# STM32F4layout.net
KiCad netlist of a schematic drawn in EAGLE
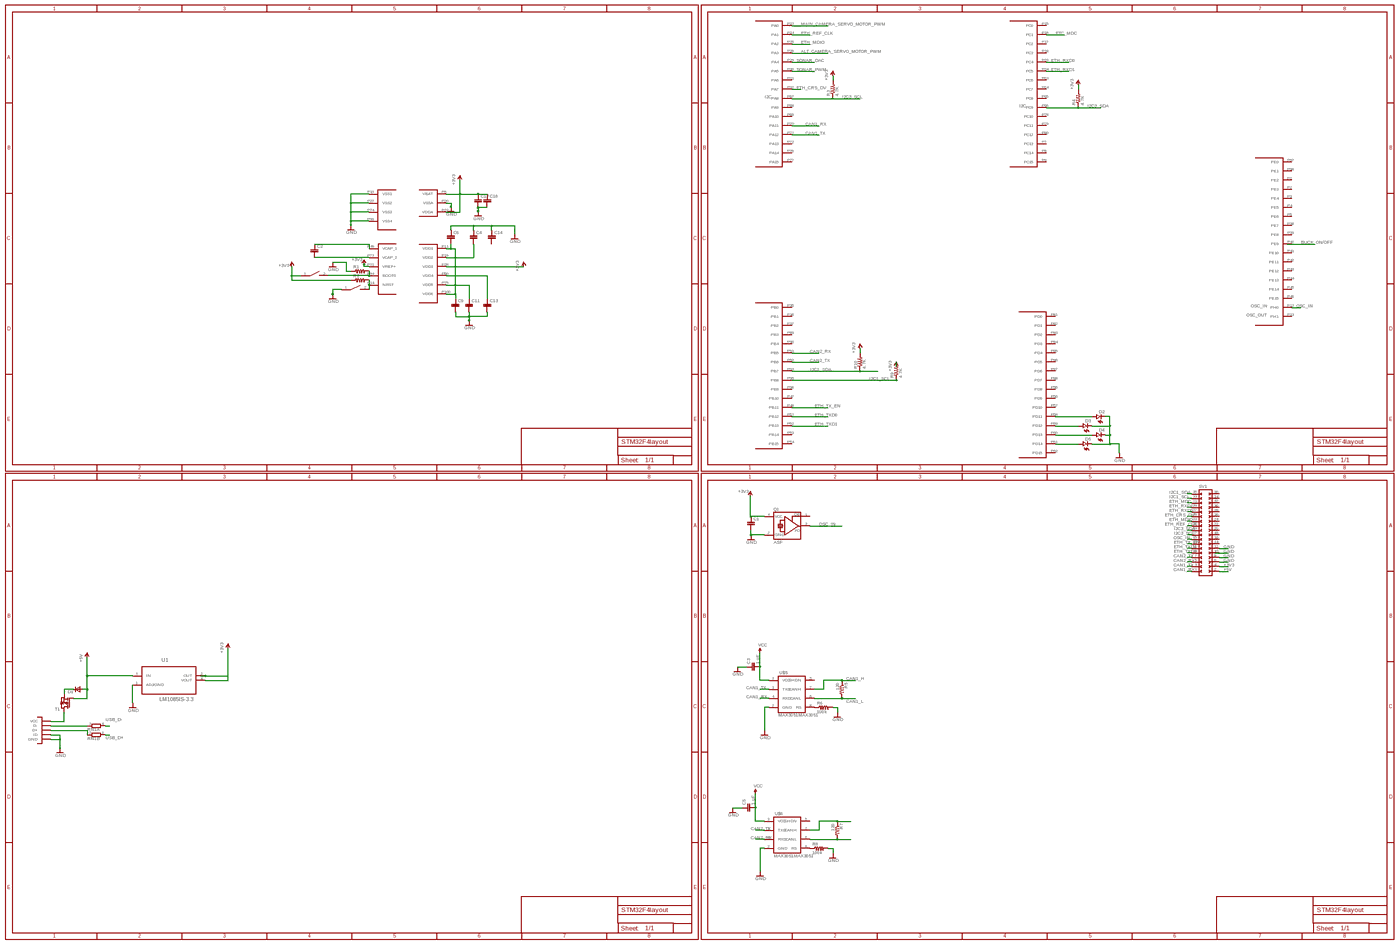
[diagram p0: schematic, sheet 1, overview]
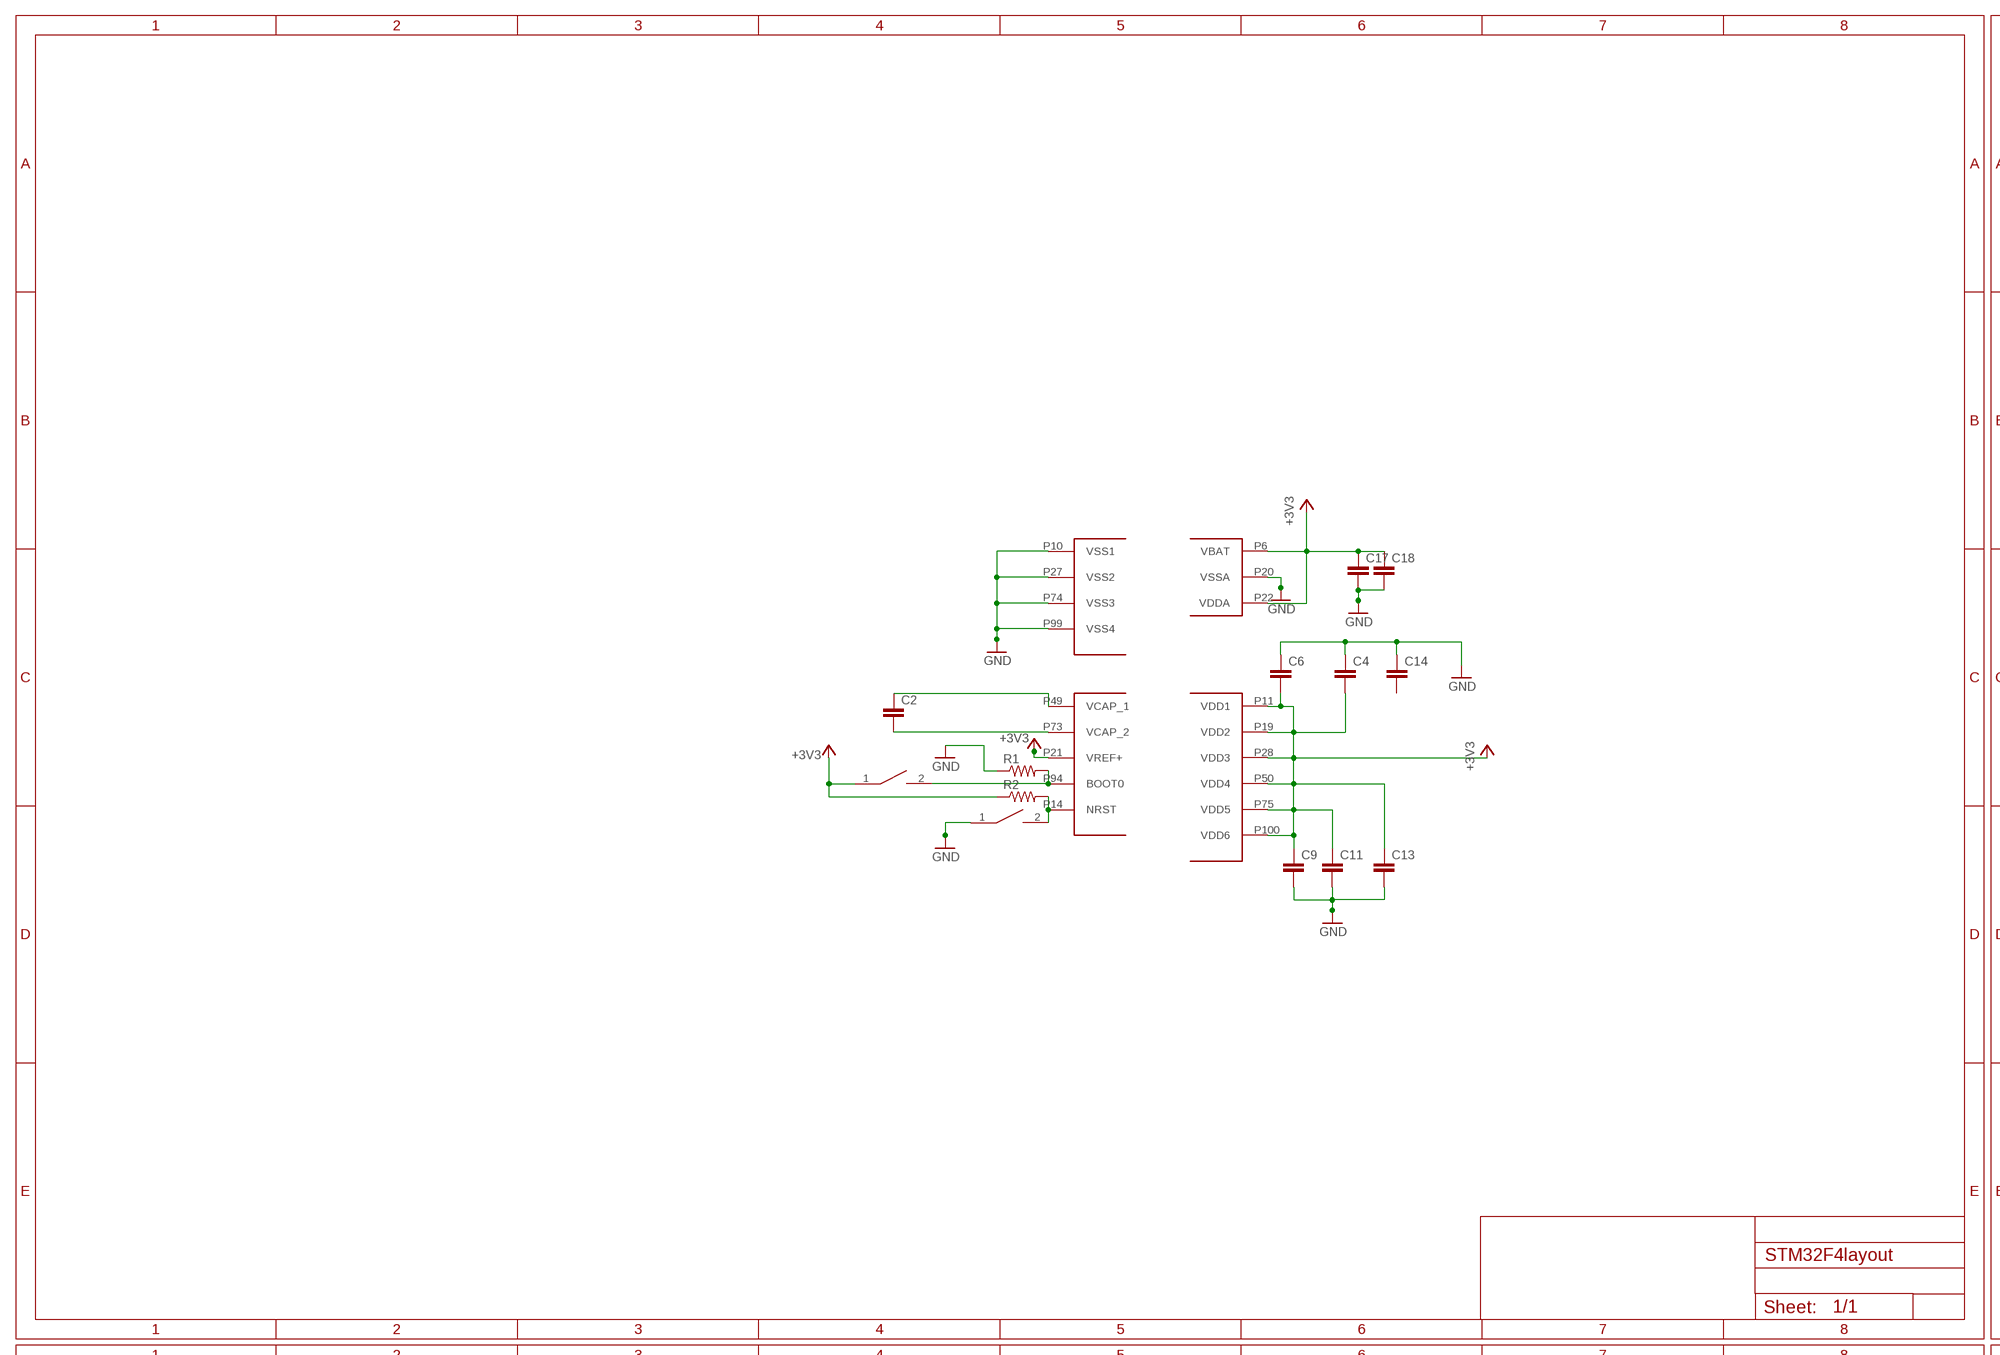
[diagram p1: schematic, sheet 1, part 1 of 4]
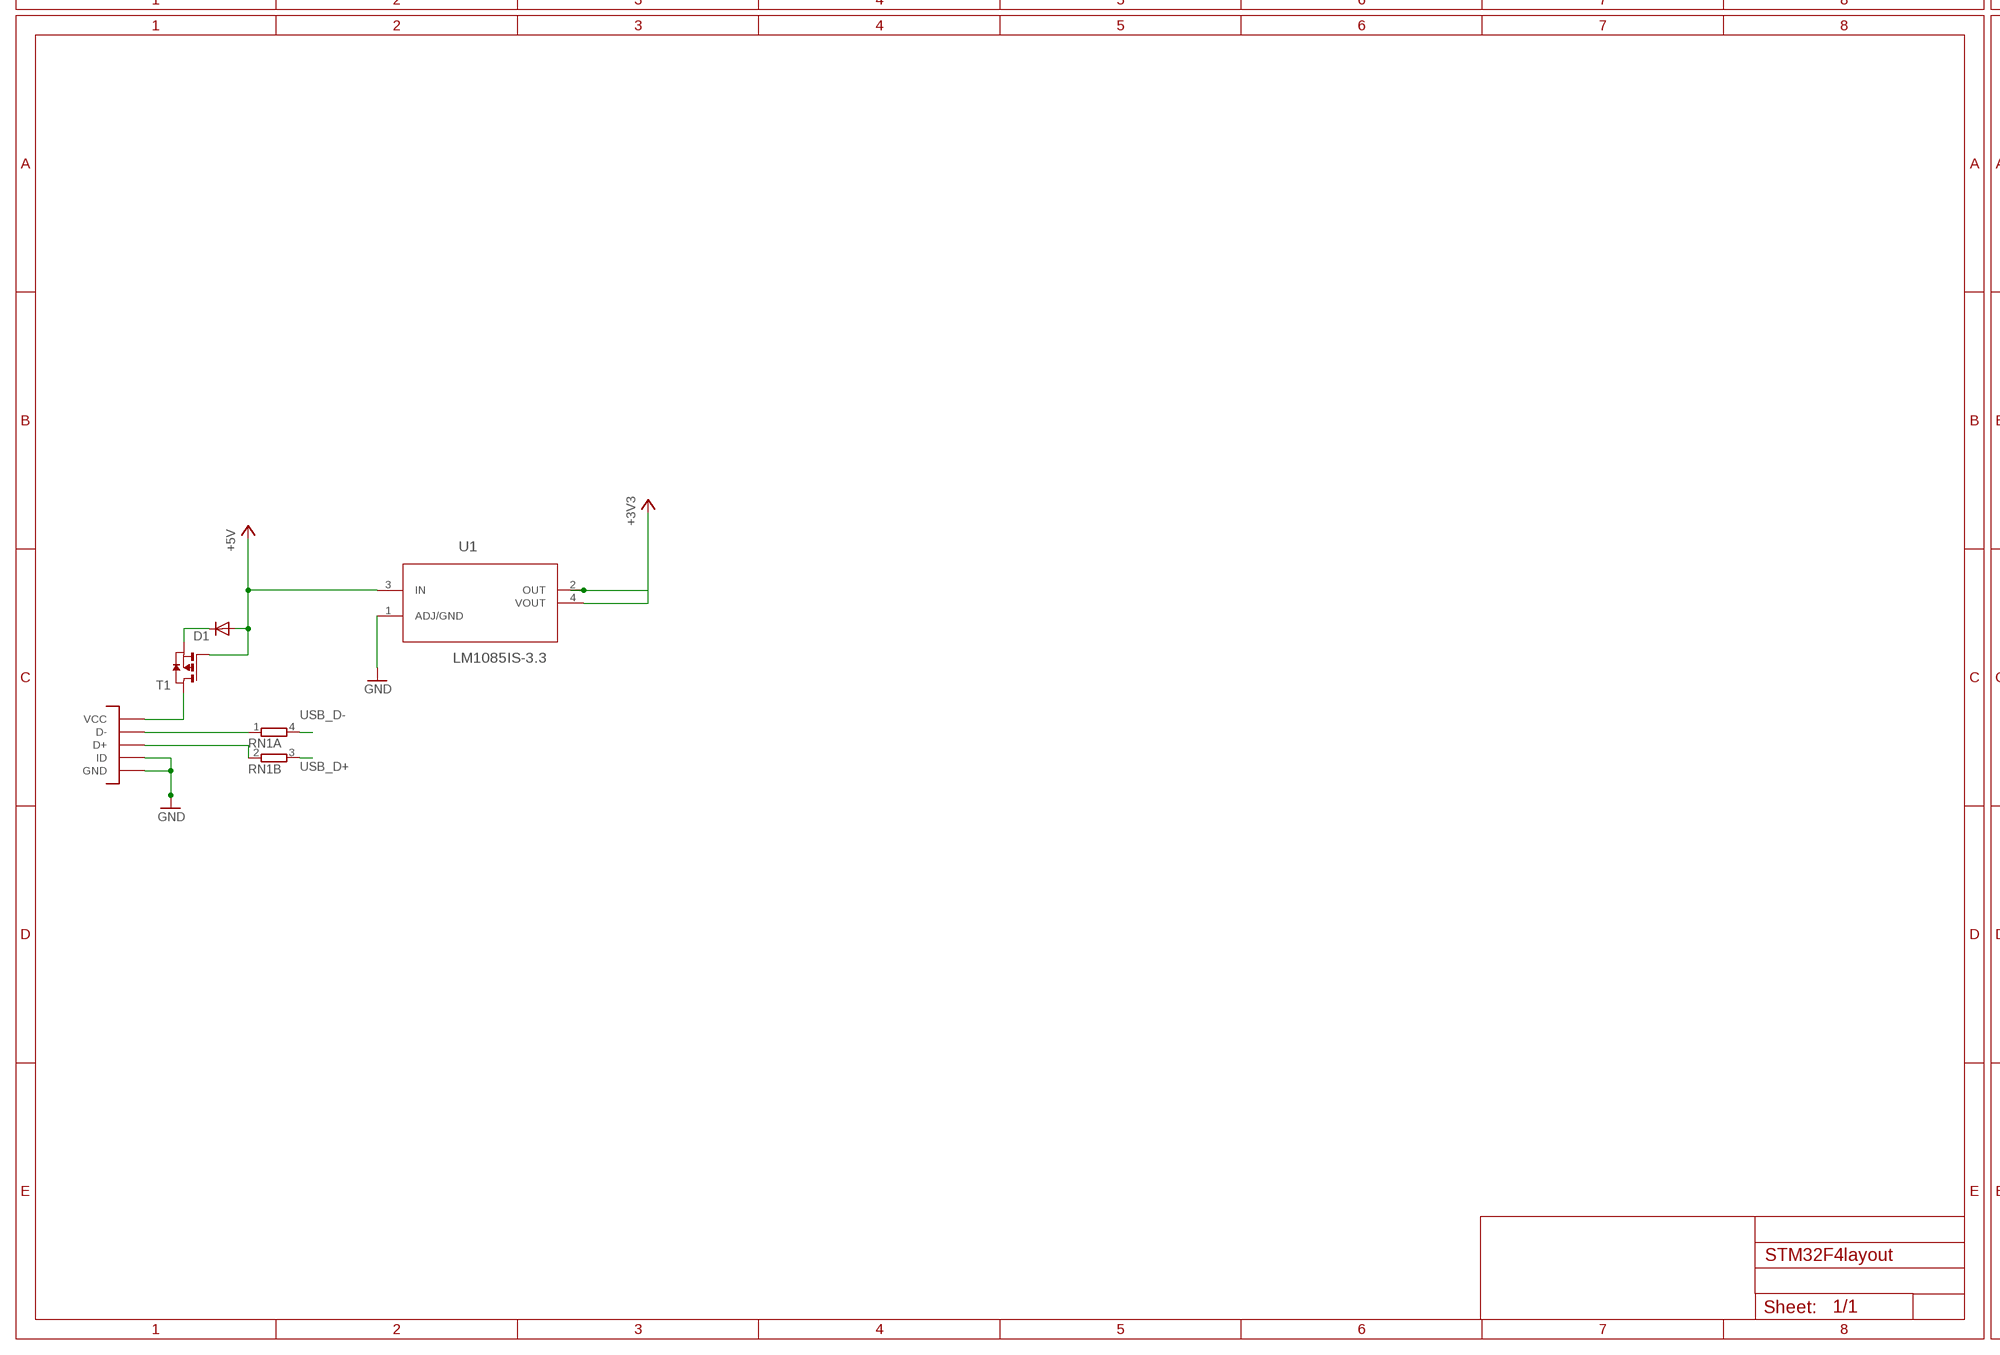
[diagram p2: schematic, sheet 1, part 2 of 4]
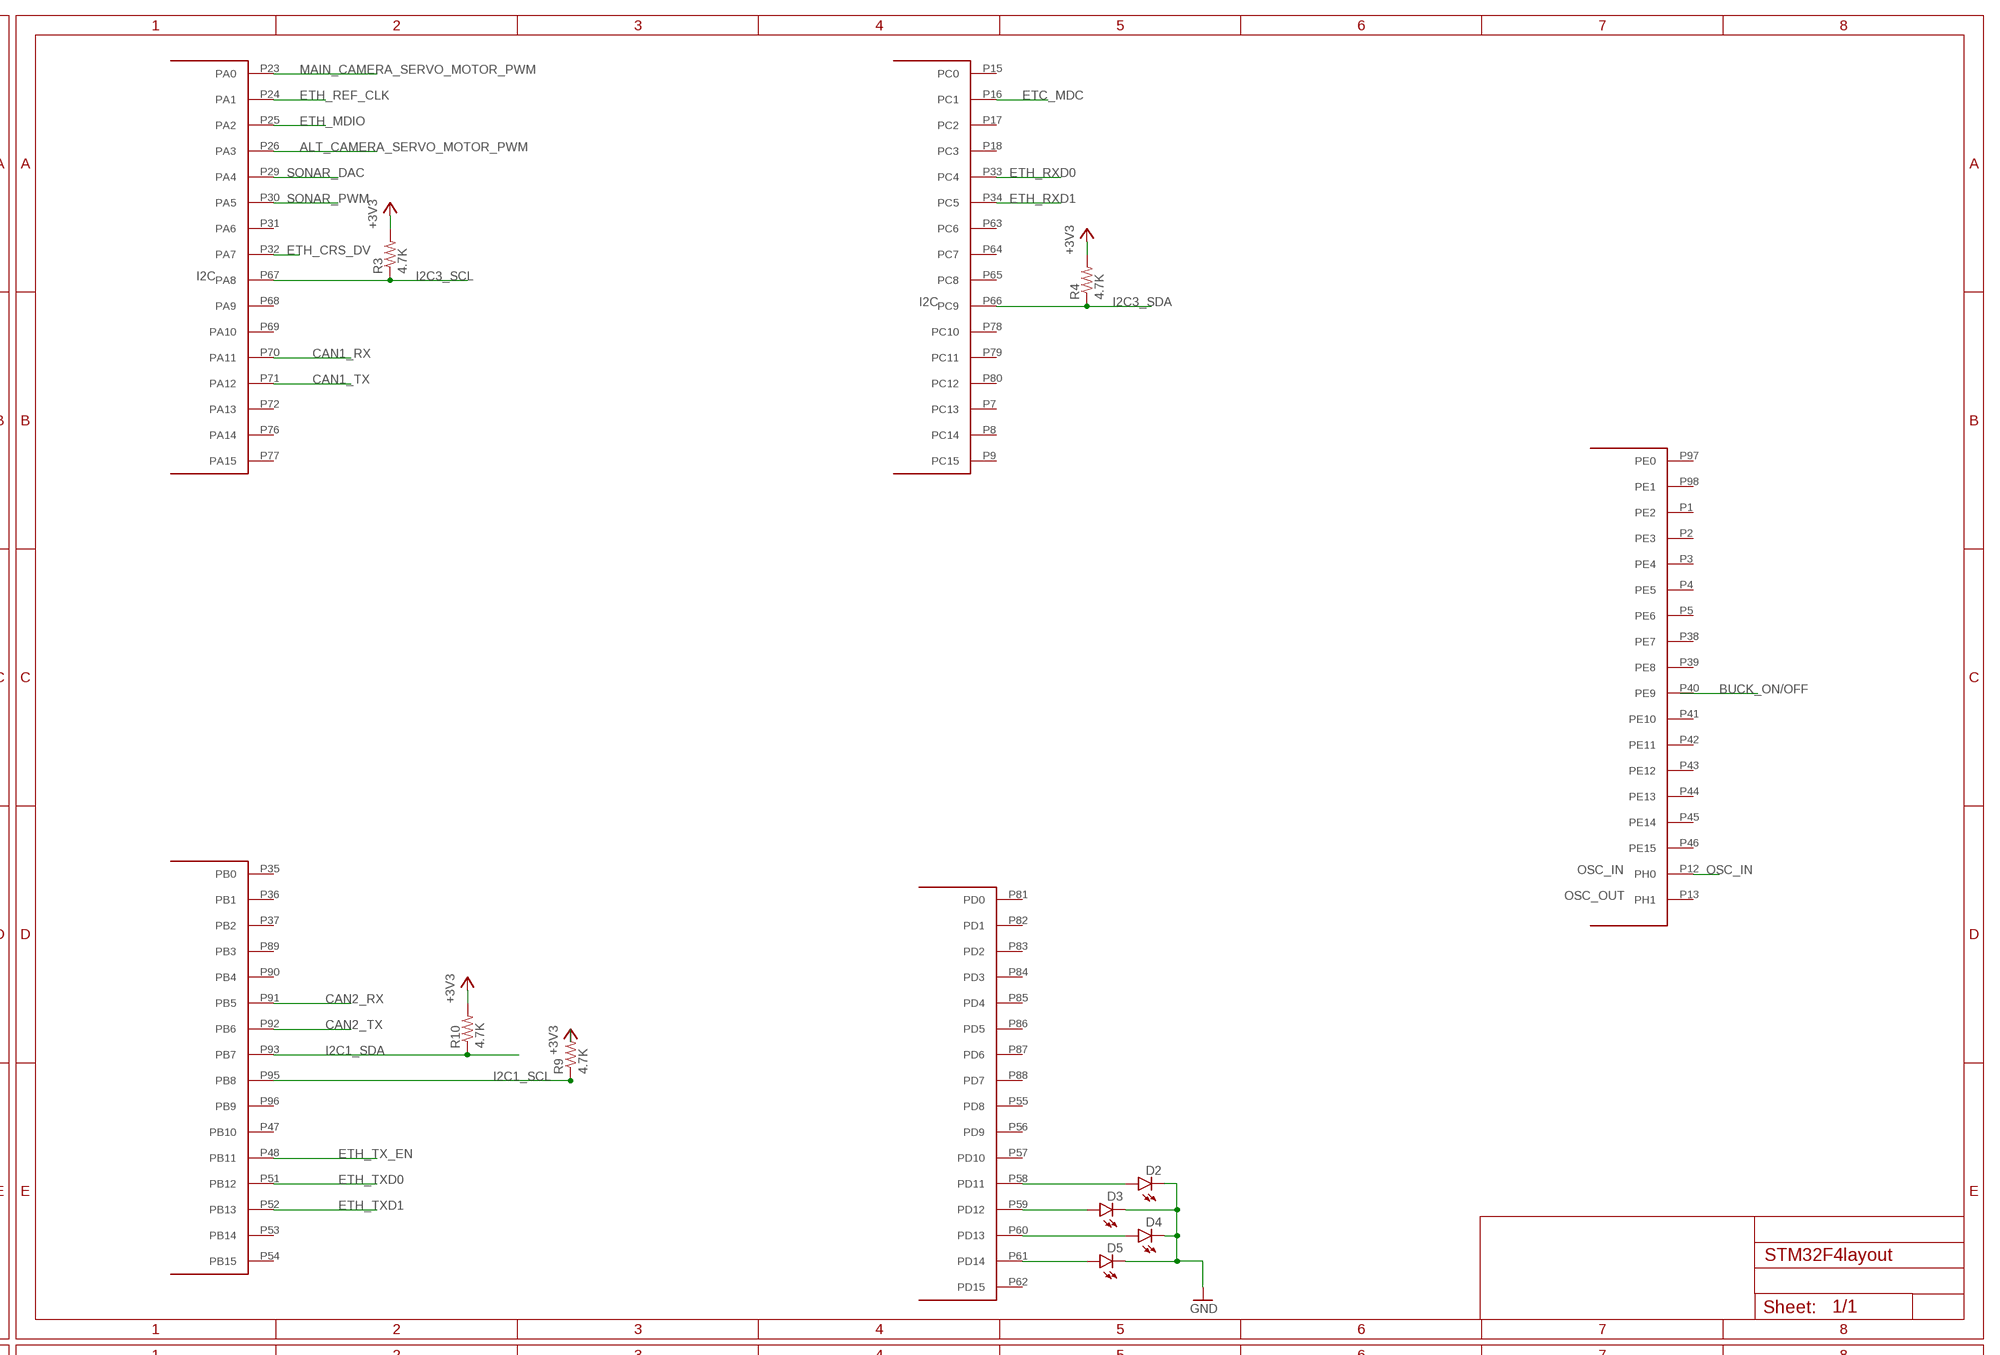
[diagram p3: schematic, sheet 1, part 3 of 4]
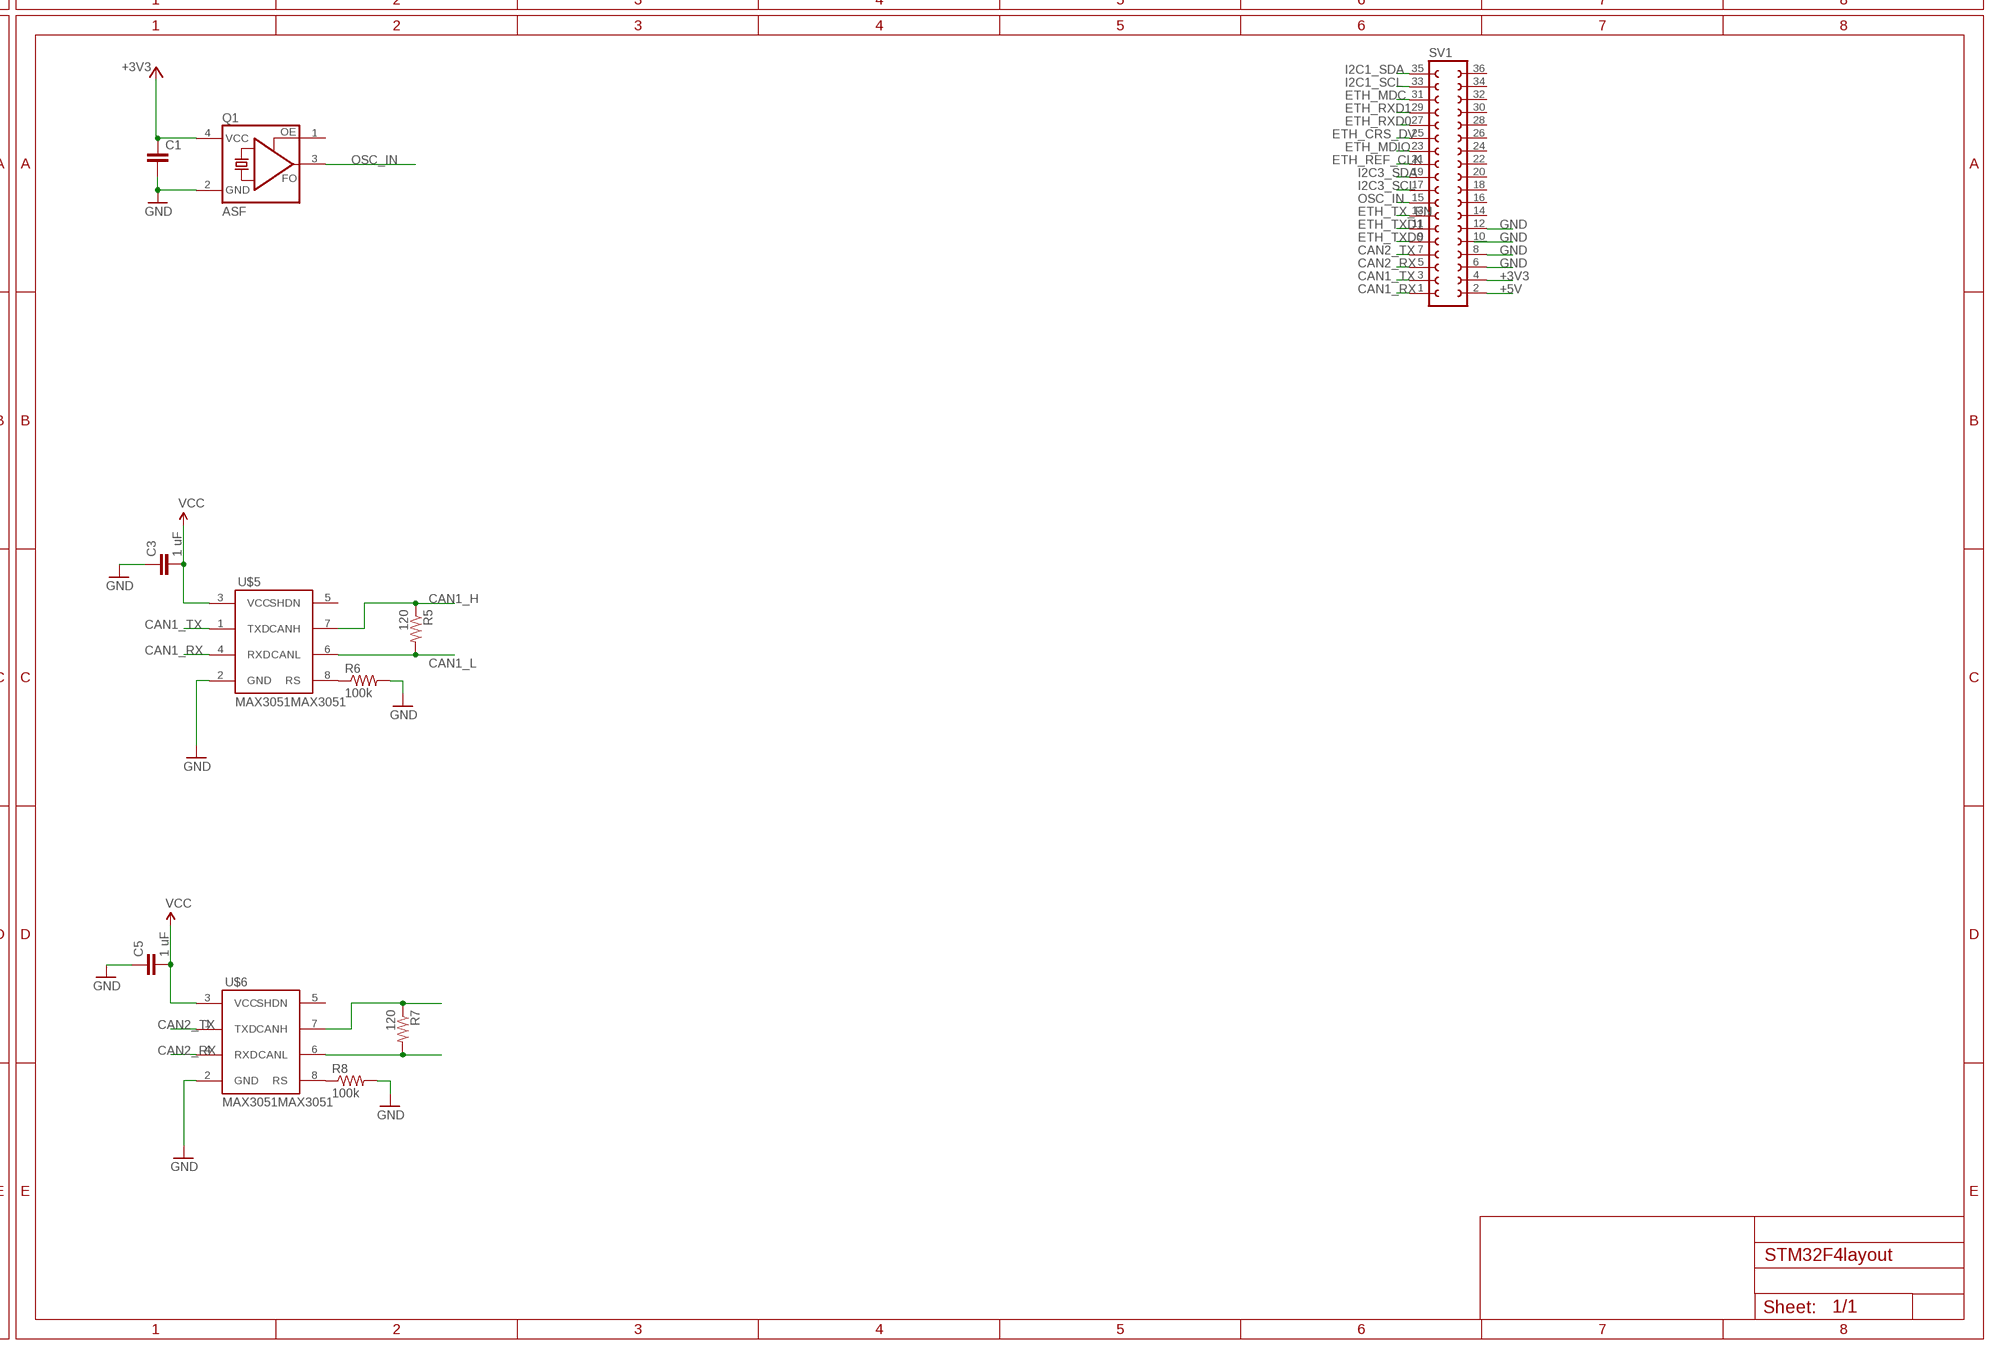
[diagram p4: schematic, sheet 1, part 4 of 4]

(export (version "E")
  (design (tool "Eeschema 10.0.6"))
  (components
    (comp (ref "C1")
      (value "CAP0603-CAP")
      (footprint "eagle-import:0603-CAP")
      (libsource (lib "eagle-import") (part "CAP0603-CAP"))
    )
    (comp (ref "C2")
      (value "CAP0603-CAP")
      (footprint "eagle-import:0603-CAP")
      (libsource (lib "eagle-import") (part "CAP0603-CAP"))
    )
    (comp (ref "C3")
      (value "1 uF")
      (footprint "eagle-import:C2.5-3")
      (libsource (lib "eagle-import") (part "C2,5-3"))
    )
    (comp (ref "C4")
      (value "CAP0603-CAP")
      (footprint "eagle-import:0603-CAP")
      (libsource (lib "eagle-import") (part "CAP0603-CAP"))
    )
    (comp (ref "C5")
      (value "1 uF")
      (footprint "eagle-import:C2.5-3")
      (libsource (lib "eagle-import") (part "C2,5-3"))
    )
    (comp (ref "C6")
      (value "CAP0603-CAP")
      (footprint "eagle-import:0603-CAP")
      (libsource (lib "eagle-import") (part "CAP0603-CAP"))
    )
    (comp (ref "C9")
      (value "CAP0603-CAP")
      (footprint "eagle-import:0603-CAP")
      (libsource (lib "eagle-import") (part "CAP0603-CAP"))
    )
    (comp (ref "C11")
      (value "CAP0603-CAP")
      (footprint "eagle-import:0603-CAP")
      (libsource (lib "eagle-import") (part "CAP0603-CAP"))
    )
    (comp (ref "C13")
      (value "CAP0603-CAP")
      (footprint "eagle-import:0603-CAP")
      (libsource (lib "eagle-import") (part "CAP0603-CAP"))
    )
    (comp (ref "C14")
      (value "CAP0603-CAP")
      (footprint "eagle-import:0603-CAP")
      (libsource (lib "eagle-import") (part "CAP0603-CAP"))
    )
    (comp (ref "C17")
      (value "CAP0603-CAP")
      (footprint "eagle-import:0603-CAP")
      (libsource (lib "eagle-import") (part "CAP0603-CAP"))
    )
    (comp (ref "C18")
      (value "CAP0603-CAP")
      (footprint "eagle-import:0603-CAP")
      (libsource (lib "eagle-import") (part "CAP0603-CAP"))
    )
    (comp (ref "D1")
      (value "DIODE-DO-214AC")
      (footprint "eagle-import:DO-214AC")
      (libsource (lib "eagle-import") (part "DIODE-DO-214AC"))
    )
    (comp (ref "D2")
      (value "LED0603")
      (footprint "eagle-import:LED-0603")
      (libsource (lib "eagle-import") (part "LED0603"))
    )
    (comp (ref "D3")
      (value "LED0603")
      (footprint "eagle-import:LED-0603")
      (libsource (lib "eagle-import") (part "LED0603"))
    )
    (comp (ref "D4")
      (value "LED0603")
      (footprint "eagle-import:LED-0603")
      (libsource (lib "eagle-import") (part "LED0603"))
    )
    (comp (ref "D5")
      (value "LED0603")
      (footprint "eagle-import:LED-0603")
      (libsource (lib "eagle-import") (part "LED0603"))
    )
    (comp (ref "Q1")
      (value "ASF")
      (footprint "eagle-import:ASF")
      (libsource (lib "eagle-import") (part "ASF"))
    )
    (comp (ref "R1")
      (value "RESISTOR0603-RES")
      (footprint "eagle-import:0603-RES")
      (libsource (lib "eagle-import") (part "RESISTOR0603-RES"))
    )
    (comp (ref "R2")
      (value "RESISTOR0603-RES")
      (footprint "eagle-import:0603-RES")
      (libsource (lib "eagle-import") (part "RESISTOR0603-RES"))
    )
    (comp (ref "R3")
      (value "4.7K")
      (footprint "eagle-import:0603-RES")
      (libsource (lib "eagle-import") (part "RESISTOR0603-RES"))
    )
    (comp (ref "R4")
      (value "4.7K")
      (footprint "eagle-import:0603-RES")
      (libsource (lib "eagle-import") (part "RESISTOR0603-RES"))
    )
    (comp (ref "R5")
      (value "120")
      (footprint "eagle-import:0204V")
      (libsource (lib "eagle-import") (part "R-US_0204/2V"))
    )
    (comp (ref "R6")
      (value "100k")
      (footprint "eagle-import:0204V")
      (libsource (lib "eagle-import") (part "R-US_0204/2V"))
    )
    (comp (ref "R7")
      (value "120")
      (footprint "eagle-import:0204V")
      (libsource (lib "eagle-import") (part "R-US_0204/2V"))
    )
    (comp (ref "R8")
      (value "100k")
      (footprint "eagle-import:0204V")
      (libsource (lib "eagle-import") (part "R-US_0204/2V"))
    )
    (comp (ref "R9")
      (value "4.7K")
      (footprint "eagle-import:0603-RES")
      (libsource (lib "eagle-import") (part "RESISTOR0603-RES"))
    )
    (comp (ref "R10")
      (value "4.7K")
      (footprint "eagle-import:0603-RES")
      (libsource (lib "eagle-import") (part "RESISTOR0603-RES"))
    )
    (comp (ref "RN1")
      (value "2R-NEXBV4V")
      (footprint "eagle-import:EXBV4V")
      (fields (field (name "MF") "Rohm Semiconductor") (field (name "MPN") "MNR12ERAPJ220"))
      (libsource (lib "eagle-import") (part "2R-NEXBV4V"))
    )
    (comp (ref "SV1")
      (value "FE18-2")
      (footprint "eagle-import:FE18-2")
      (libsource (lib "eagle-import") (part "FE18-2"))
    )
    (comp (ref "T1")
      (value "FDN340P")
      (footprint "eagle-import:SOT-23")
      (libsource (lib "eagle-import") (part "FDN340P"))
    )
    (comp (ref "U$1")
      (value "STM32F4")
      (footprint "eagle-import:LQFP100")
      (libsource (lib "eagle-import") (part "STM32F4"))
    )
    (comp (ref "U$2")
      (value "SWITCH")
      (footprint "eagle-import:SW_2512")
      (libsource (lib "eagle-import") (part "SWITCH"))
    )
    (comp (ref "U$3")
      (value "SWITCH")
      (footprint "eagle-import:SW_2512")
      (libsource (lib "eagle-import") (part "SWITCH"))
    )
    (comp (ref "U$4")
      (value "MICROUSB")
      (footprint "eagle-import:MICRO_B")
      (libsource (lib "eagle-import") (part "MICROUSB"))
    )
    (comp (ref "U$5")
      (value "MAX3051MAX3051")
      (footprint "eagle-import:SOT23-8L")
      (libsource (lib "eagle-import") (part "MAX3051MAX3051"))
    )
    (comp (ref "U$6")
      (value "MAX3051MAX3051")
      (footprint "eagle-import:SOT23-8L")
      (libsource (lib "eagle-import") (part "MAX3051MAX3051"))
    )
    (comp (ref "U1")
      (value "LM1085IS-3.3")
      (footprint "eagle-import:TO254P1435X457-3N")
      (libsource (lib "eagle-import") (part "LM1085IS-3.3"))
    )
  )
  (nets
    (net (code "1") (name "+3V3") (class "Default")
      (node (ref "C11") (pin "1") (pinfunction "1_1") (pintype "passive"))
      (node (ref "C13") (pin "1") (pinfunction "1_1") (pintype "passive"))
      (node (ref "C17") (pin "1") (pinfunction "1_1") (pintype "passive"))
      (node (ref "C18") (pin "1") (pinfunction "1_1") (pintype "passive"))
      (node (ref "C4") (pin "2") (pinfunction "2_2") (pintype "passive"))
      (node (ref "C6") (pin "2") (pinfunction "2_2") (pintype "passive"))
      (node (ref "C9") (pin "1") (pinfunction "1_1") (pintype "passive"))
      (node (ref "R10") (pin "2") (pinfunction "2_2") (pintype "passive"))
      (node (ref "R2") (pin "1") (pinfunction "1_1") (pintype "passive"))
      (node (ref "R3") (pin "2") (pinfunction "2_2") (pintype "passive"))
      (node (ref "R4") (pin "2") (pinfunction "2_2") (pintype "passive"))
      (node (ref "R9") (pin "2") (pinfunction "2_2") (pintype "passive"))
      (node (ref "SV1") (pin "4") (pinfunction "4_4") (pintype "passive"))
      (node (ref "U$1") (pin "P100") (pinfunction "VDD6_P100") (pintype "bidirectional"))
      (node (ref "U$1") (pin "P11") (pinfunction "VDD1_P11") (pintype "bidirectional"))
      (node (ref "U$1") (pin "P19") (pinfunction "VDD2_P19") (pintype "bidirectional"))
      (node (ref "U$1") (pin "P21") (pinfunction "VREF+_P21") (pintype "bidirectional"))
      (node (ref "U$1") (pin "P22") (pinfunction "VDDA_P22") (pintype "bidirectional"))
      (node (ref "U$1") (pin "P28") (pinfunction "VDD3_P28") (pintype "bidirectional"))
      (node (ref "U$1") (pin "P50") (pinfunction "VDD4_P50") (pintype "bidirectional"))
      (node (ref "U$1") (pin "P6") (pinfunction "VBAT_P6") (pintype "bidirectional"))
      (node (ref "U$1") (pin "P75") (pinfunction "VDD5_P75") (pintype "bidirectional"))
      (node (ref "U$3") (pin "1") (pinfunction "P$1_1") (pintype "bidirectional"))
      (node (ref "U1") (pin "2") (pinfunction "OUT_2") (pintype "output"))
      (node (ref "U1") (pin "4") (pinfunction "VOUT_4") (pintype "output"))
    )
    (net (code "2") (name "+5V") (class "Default")
      (node (ref "D1") (pin "A") (pinfunction "A_A") (pintype "passive"))
      (node (ref "SV1") (pin "2") (pinfunction "2_2") (pintype "passive"))
      (node (ref "T1") (pin "3") (pinfunction "G_3") (pintype "passive"))
      (node (ref "U1") (pin "3") (pinfunction "IN_3") (pintype "power_in"))
    )
    (net (code "3") (name "/ALT_CAMERA_SERVO_MOTOR_PWM") (class "Default")
      (node (ref "U$1") (pin "P26") (pinfunction "PA3_P26") (pintype "bidirectional"))
    )
    (net (code "5") (name "/CAN1_H") (class "Default")
      (node (ref "R5") (pin "1") (pinfunction "1_1") (pintype "passive"))
      (node (ref "U$5") (pin "7") (pinfunction "CANH_7") (pintype "bidirectional"))
    )
    (net (code "6") (name "/CAN1_L") (class "Default")
      (node (ref "R5") (pin "2") (pinfunction "2_2") (pintype "passive"))
      (node (ref "U$5") (pin "6") (pinfunction "CANL_6") (pintype "bidirectional"))
    )
    (net (code "7") (name "/CAN1_RX") (class "Default")
      (node (ref "RN1") (pin "4") (pinfunction "2_4") (pintype "passive"))
      (node (ref "SV1") (pin "1") (pinfunction "1_1") (pintype "passive"))
      (node (ref "U$1") (pin "P70") (pinfunction "PA11_P70") (pintype "bidirectional"))
      (node (ref "U$5") (pin "4") (pinfunction "RXD_4") (pintype "bidirectional"))
    )
    (net (code "8") (name "/CAN1_TX") (class "Default")
      (node (ref "RN1") (pin "3") (pinfunction "2_3") (pintype "passive"))
      (node (ref "SV1") (pin "3") (pinfunction "3_3") (pintype "passive"))
      (node (ref "U$1") (pin "P71") (pinfunction "PA12_P71") (pintype "bidirectional"))
      (node (ref "U$5") (pin "1") (pinfunction "TXD_1") (pintype "bidirectional"))
    )
    (net (code "9") (name "/CAN2_RX") (class "Default")
      (node (ref "SV1") (pin "5") (pinfunction "5_5") (pintype "passive"))
      (node (ref "U$1") (pin "P91") (pinfunction "PB5_P91") (pintype "bidirectional"))
      (node (ref "U$6") (pin "4") (pinfunction "RXD_4") (pintype "bidirectional"))
    )
    (net (code "10") (name "/CAN2_TX") (class "Default")
      (node (ref "SV1") (pin "7") (pinfunction "7_7") (pintype "passive"))
      (node (ref "U$1") (pin "P92") (pinfunction "PB6_P92") (pintype "bidirectional"))
      (node (ref "U$6") (pin "1") (pinfunction "TXD_1") (pintype "bidirectional"))
    )
    (net (code "11") (name "/ETC_MDC") (class "Default")
      (node (ref "U$1") (pin "P16") (pinfunction "PC1_P16") (pintype "bidirectional"))
    )
    (net (code "12") (name "/ETH_CRS_DV") (class "Default")
      (node (ref "SV1") (pin "25") (pinfunction "25_25") (pintype "passive"))
      (node (ref "U$1") (pin "P32") (pinfunction "PA7_P32") (pintype "bidirectional"))
    )
    (net (code "13") (name "/ETH_MDC") (class "Default")
      (node (ref "SV1") (pin "31") (pinfunction "31_31") (pintype "passive"))
    )
    (net (code "14") (name "/ETH_MDIO") (class "Default")
      (node (ref "SV1") (pin "23") (pinfunction "23_23") (pintype "passive"))
      (node (ref "U$1") (pin "P25") (pinfunction "PA2_P25") (pintype "bidirectional"))
    )
    (net (code "15") (name "/ETH_REF_CLK") (class "Default")
      (node (ref "SV1") (pin "21") (pinfunction "21_21") (pintype "passive"))
      (node (ref "U$1") (pin "P24") (pinfunction "PA1_P24") (pintype "bidirectional"))
    )
    (net (code "16") (name "/ETH_RXD0") (class "Default")
      (node (ref "SV1") (pin "27") (pinfunction "27_27") (pintype "passive"))
      (node (ref "U$1") (pin "P33") (pinfunction "PC4_P33") (pintype "bidirectional"))
    )
    (net (code "17") (name "/ETH_RXD1") (class "Default")
      (node (ref "SV1") (pin "29") (pinfunction "29_29") (pintype "passive"))
      (node (ref "U$1") (pin "P34") (pinfunction "PC5_P34") (pintype "bidirectional"))
    )
    (net (code "18") (name "/ETH_TXD0") (class "Default")
      (node (ref "SV1") (pin "9") (pinfunction "9_9") (pintype "passive"))
      (node (ref "U$1") (pin "P51") (pinfunction "PB12_P51") (pintype "bidirectional"))
    )
    (net (code "19") (name "/ETH_TXD1") (class "Default")
      (node (ref "SV1") (pin "11") (pinfunction "11_11") (pintype "passive"))
      (node (ref "U$1") (pin "P52") (pinfunction "PB13_P52") (pintype "bidirectional"))
    )
    (net (code "20") (name "/ETH_TX_EN") (class "Default")
      (node (ref "SV1") (pin "13") (pinfunction "13_13") (pintype "passive"))
      (node (ref "U$1") (pin "P48") (pinfunction "PB11_P48") (pintype "bidirectional"))
    )
    (net (code "21") (name "/I2C1_SCL") (class "Default")
      (node (ref "R9") (pin "1") (pinfunction "1_1") (pintype "passive"))
      (node (ref "SV1") (pin "33") (pinfunction "33_33") (pintype "passive"))
      (node (ref "U$1") (pin "P95") (pinfunction "PB8_P95") (pintype "bidirectional"))
    )
    (net (code "22") (name "/I2C1_SDA") (class "Default")
      (node (ref "R10") (pin "1") (pinfunction "1_1") (pintype "passive"))
      (node (ref "SV1") (pin "35") (pinfunction "35_35") (pintype "passive"))
      (node (ref "U$1") (pin "P93") (pinfunction "PB7_P93") (pintype "bidirectional"))
    )
    (net (code "23") (name "/I2C3_SCL") (class "Default")
      (node (ref "R3") (pin "1") (pinfunction "1_1") (pintype "passive"))
      (node (ref "SV1") (pin "17") (pinfunction "17_17") (pintype "passive"))
      (node (ref "U$1") (pin "P67") (pinfunction "PA8_P67") (pintype "bidirectional"))
    )
    (net (code "24") (name "/I2C3_SDA") (class "Default")
      (node (ref "R4") (pin "1") (pinfunction "1_1") (pintype "passive"))
      (node (ref "SV1") (pin "19") (pinfunction "19_19") (pintype "passive"))
      (node (ref "U$1") (pin "P66") (pinfunction "PC9_P66") (pintype "bidirectional"))
    )
    (net (code "25") (name "/MAIN_CAMERA_SERVO_MOTOR_PWM") (class "Default")
      (node (ref "U$1") (pin "P23") (pinfunction "PA0_P23") (pintype "bidirectional"))
    )
    (net (code "26") (name "/OSC_IN") (class "Default")
      (node (ref "Q1") (pin "3") (pinfunction "FO_3") (pintype "output"))
      (node (ref "SV1") (pin "15") (pinfunction "15_15") (pintype "passive"))
      (node (ref "U$1") (pin "P12") (pinfunction "PH0_P12") (pintype "bidirectional"))
    )
    (net (code "27") (name "/SONAR_DAC") (class "Default")
      (node (ref "U$1") (pin "P29") (pinfunction "PA4_P29") (pintype "bidirectional"))
    )
    (net (code "28") (name "/SONAR_PWM") (class "Default")
      (node (ref "U$1") (pin "P30") (pinfunction "PA5_P30") (pintype "bidirectional"))
    )
    (net (code "29") (name "GND") (class "Default")
      (node (ref "C1") (pin "2") (pinfunction "2_2") (pintype "passive"))
      (node (ref "C11") (pin "2") (pinfunction "2_2") (pintype "passive"))
      (node (ref "C13") (pin "2") (pinfunction "2_2") (pintype "passive"))
      (node (ref "C14") (pin "1") (pinfunction "1_1") (pintype "passive"))
      (node (ref "C17") (pin "2") (pinfunction "2_2") (pintype "passive"))
      (node (ref "C18") (pin "2") (pinfunction "2_2") (pintype "passive"))
      (node (ref "C3") (pin "1") (pinfunction "1_1") (pintype "passive"))
      (node (ref "C4") (pin "1") (pinfunction "1_1") (pintype "passive"))
      (node (ref "C5") (pin "1") (pinfunction "1_1") (pintype "passive"))
      (node (ref "C6") (pin "1") (pinfunction "1_1") (pintype "passive"))
      (node (ref "C9") (pin "2") (pinfunction "2_2") (pintype "passive"))
      (node (ref "D2") (pin "C") (pinfunction "C_C") (pintype "passive"))
      (node (ref "D3") (pin "C") (pinfunction "C_C") (pintype "passive"))
      (node (ref "D4") (pin "C") (pinfunction "C_C") (pintype "passive"))
      (node (ref "D5") (pin "C") (pinfunction "C_C") (pintype "passive"))
      (node (ref "Q1") (pin "2") (pinfunction "GND_2") (pintype "power_in"))
      (node (ref "R1") (pin "1") (pinfunction "1_1") (pintype "passive"))
      (node (ref "R6") (pin "2") (pinfunction "2_2") (pintype "passive"))
      (node (ref "R8") (pin "2") (pinfunction "2_2") (pintype "passive"))
      (node (ref "SV1") (pin "12") (pinfunction "12_12") (pintype "passive"))
      (node (ref "SV1") (pin "6") (pinfunction "6_6") (pintype "passive"))
      (node (ref "SV1") (pin "8") (pinfunction "8_8") (pintype "passive"))
      (node (ref "U$1") (pin "P10") (pinfunction "VSS1_P10") (pintype "bidirectional"))
      (node (ref "U$1") (pin "P20") (pinfunction "VSSA_P20") (pintype "bidirectional"))
      (node (ref "U$1") (pin "P27") (pinfunction "VSS2_P27") (pintype "bidirectional"))
      (node (ref "U$1") (pin "P74") (pinfunction "VSS3_P74") (pintype "bidirectional"))
      (node (ref "U$1") (pin "P99") (pinfunction "VSS4_P99") (pintype "bidirectional"))
      (node (ref "U$2") (pin "1") (pinfunction "P$1_1") (pintype "bidirectional"))
      (node (ref "U$4") (pin "GND1") (pinfunction "GND_GND1") (pintype "bidirectional"))
      (node (ref "U$4") (pin "GND2") (pinfunction "GND_GND2") (pintype "bidirectional"))
      (node (ref "U$4") (pin "GND3") (pinfunction "GND_GND3") (pintype "bidirectional"))
      (node (ref "U$4") (pin "GND4") (pinfunction "GND_GND4") (pintype "bidirectional"))
      (node (ref "U$4") (pin "GND7") (pinfunction "GND_GND7") (pintype "bidirectional"))
      (node (ref "U$4") (pin "GND8") (pinfunction "GND_GND8") (pintype "bidirectional"))
      (node (ref "U$4") (pin "P4") (pinfunction "ID_P4") (pintype "bidirectional"))
      (node (ref "U$4") (pin "P5") (pinfunction "GND_P5") (pintype "bidirectional"))
      (node (ref "U$5") (pin "2") (pinfunction "GND_2") (pintype "bidirectional"))
      (node (ref "U$6") (pin "2") (pinfunction "GND_2") (pintype "bidirectional"))
      (node (ref "U1") (pin "1") (pinfunction "ADJ/GND_1") (pintype "passive"))
    )
    (net (code "30") (name "Net-(Q1-VCC)") (class "Default")
      (node (ref "C1") (pin "1") (pinfunction "1_1") (pintype "passive"))
      (node (ref "Q1") (pin "4") (pinfunction "VCC_4") (pintype "power_in"))
    )
    (net (code "31") (name "Net-(RN1B-1)") (class "Default")
      (node (ref "RN1") (pin "2") (pinfunction "1_2") (pintype "passive"))
      (node (ref "U$4") (pin "P3") (pinfunction "D+_P3") (pintype "bidirectional"))
    )
    (net (code "32") (name "Net-(T1-D)") (class "Default")
      (node (ref "T1") (pin "1") (pinfunction "D_1") (pintype "passive"))
      (node (ref "U$4") (pin "P1") (pinfunction "VCC_P1") (pintype "bidirectional"))
    )
    (net (code "33") (name "Net-(T1-S)") (class "Default")
      (node (ref "D1") (pin "C") (pinfunction "C_C") (pintype "passive"))
      (node (ref "T1") (pin "2") (pinfunction "S_2") (pintype "passive"))
    )
    (net (code "34") (name "Net-(U$1D-PD11)") (class "Default")
      (node (ref "D2") (pin "A") (pinfunction "A_A") (pintype "passive"))
      (node (ref "U$1") (pin "P58") (pinfunction "PD11_P58") (pintype "bidirectional"))
    )
    (net (code "35") (name "Net-(U$1D-PD12)") (class "Default")
      (node (ref "D3") (pin "A") (pinfunction "A_A") (pintype "passive"))
      (node (ref "U$1") (pin "P59") (pinfunction "PD12_P59") (pintype "bidirectional"))
    )
    (net (code "36") (name "Net-(U$1D-PD13)") (class "Default")
      (node (ref "D4") (pin "A") (pinfunction "A_A") (pintype "passive"))
      (node (ref "U$1") (pin "P60") (pinfunction "PD13_P60") (pintype "bidirectional"))
    )
    (net (code "37") (name "Net-(U$1D-PD14)") (class "Default")
      (node (ref "D5") (pin "A") (pinfunction "A_A") (pintype "passive"))
      (node (ref "U$1") (pin "P61") (pinfunction "PD14_P61") (pintype "bidirectional"))
    )
    (net (code "38") (name "Net-(U$1F-BOOT0)") (class "Default")
      (node (ref "R1") (pin "2") (pinfunction "2_2") (pintype "passive"))
      (node (ref "U$1") (pin "P94") (pinfunction "BOOT0_P94") (pintype "bidirectional"))
      (node (ref "U$3") (pin "2") (pinfunction "P$2_2") (pintype "bidirectional"))
    )
    (net (code "39") (name "Net-(U$1F-NRST)") (class "Default")
      (node (ref "R2") (pin "2") (pinfunction "2_2") (pintype "passive"))
      (node (ref "U$1") (pin "P14") (pinfunction "NRST_P14") (pintype "bidirectional"))
      (node (ref "U$2") (pin "2") (pinfunction "P$2_2") (pintype "bidirectional"))
    )
    (net (code "40") (name "Net-(U$1F-VCAP_1)") (class "Default")
      (node (ref "C2") (pin "1") (pinfunction "1_1") (pintype "passive"))
      (node (ref "U$1") (pin "P49") (pinfunction "VCAP_1_P49") (pintype "bidirectional"))
    )
    (net (code "41") (name "Net-(U$1F-VCAP_2)") (class "Default")
      (node (ref "C2") (pin "2") (pinfunction "2_2") (pintype "passive"))
      (node (ref "U$1") (pin "P73") (pinfunction "VCAP_2_P73") (pintype "bidirectional"))
    )
    (net (code "42") (name "Net-(U$4-D-)") (class "Default")
      (node (ref "RN1") (pin "1") (pinfunction "1_1") (pintype "passive"))
      (node (ref "U$4") (pin "P2") (pinfunction "D-_P2") (pintype "bidirectional"))
    )
    (net (code "43") (name "Net-(U$5-RS)") (class "Default")
      (node (ref "R6") (pin "1") (pinfunction "1_1") (pintype "passive"))
      (node (ref "U$5") (pin "8") (pinfunction "RS_8") (pintype "bidirectional"))
    )
    (net (code "44") (name "Net-(U$6-CANH)") (class "Default")
      (node (ref "R7") (pin "1") (pinfunction "1_1") (pintype "passive"))
      (node (ref "U$6") (pin "7") (pinfunction "CANH_7") (pintype "bidirectional"))
    )
    (net (code "45") (name "Net-(U$6-CANL)") (class "Default")
      (node (ref "R7") (pin "2") (pinfunction "2_2") (pintype "passive"))
      (node (ref "U$6") (pin "6") (pinfunction "CANL_6") (pintype "bidirectional"))
    )
    (net (code "46") (name "Net-(U$6-RS)") (class "Default")
      (node (ref "R8") (pin "1") (pinfunction "1_1") (pintype "passive"))
      (node (ref "U$6") (pin "8") (pinfunction "RS_8") (pintype "bidirectional"))
    )
    (net (code "47") (name "VCC") (class "Default")
      (node (ref "C3") (pin "2") (pinfunction "2_2") (pintype "passive"))
      (node (ref "C5") (pin "2") (pinfunction "2_2") (pintype "passive"))
      (node (ref "U$5") (pin "3") (pinfunction "VCC_3") (pintype "bidirectional"))
      (node (ref "U$6") (pin "3") (pinfunction "VCC_3") (pintype "bidirectional"))
    )
    (net (code "48") (name "unconnected-(C14-Pad2)") (class "Default")
      (node (ref "C14") (pin "2") (pinfunction "2_2") (pintype "passive"))
    )
    (net (code "49") (name "unconnected-(Q1-OE-Pad1)") (class "Default")
      (node (ref "Q1") (pin "1") (pinfunction "OE_1") (pintype "input"))
    )
    (net (code "50") (name "unconnected-(SV1-Pad10)") (class "Default")
      (node (ref "SV1") (pin "10") (pinfunction "10_10") (pintype "passive"))
    )
    (net (code "51") (name "unconnected-(SV1-Pad14)") (class "Default")
      (node (ref "SV1") (pin "14") (pinfunction "14_14") (pintype "passive"))
    )
    (net (code "52") (name "unconnected-(SV1-Pad16)") (class "Default")
      (node (ref "SV1") (pin "16") (pinfunction "16_16") (pintype "passive"))
    )
    (net (code "53") (name "unconnected-(SV1-Pad18)") (class "Default")
      (node (ref "SV1") (pin "18") (pinfunction "18_18") (pintype "passive"))
    )
    (net (code "54") (name "unconnected-(SV1-Pad20)") (class "Default")
      (node (ref "SV1") (pin "20") (pinfunction "20_20") (pintype "passive"))
    )
    (net (code "55") (name "unconnected-(SV1-Pad22)") (class "Default")
      (node (ref "SV1") (pin "22") (pinfunction "22_22") (pintype "passive"))
    )
    (net (code "56") (name "unconnected-(SV1-Pad24)") (class "Default")
      (node (ref "SV1") (pin "24") (pinfunction "24_24") (pintype "passive"))
    )
    (net (code "57") (name "unconnected-(SV1-Pad26)") (class "Default")
      (node (ref "SV1") (pin "26") (pinfunction "26_26") (pintype "passive"))
    )
    (net (code "58") (name "unconnected-(SV1-Pad28)") (class "Default")
      (node (ref "SV1") (pin "28") (pinfunction "28_28") (pintype "passive"))
    )
    (net (code "59") (name "unconnected-(SV1-Pad30)") (class "Default")
      (node (ref "SV1") (pin "30") (pinfunction "30_30") (pintype "passive"))
    )
    (net (code "60") (name "unconnected-(SV1-Pad32)") (class "Default")
      (node (ref "SV1") (pin "32") (pinfunction "32_32") (pintype "passive"))
    )
    (net (code "61") (name "unconnected-(SV1-Pad34)") (class "Default")
      (node (ref "SV1") (pin "34") (pinfunction "34_34") (pintype "passive"))
    )
    (net (code "62") (name "unconnected-(SV1-Pad36)") (class "Default")
      (node (ref "SV1") (pin "36") (pinfunction "36_36") (pintype "passive"))
    )
    (net (code "63") (name "unconnected-(U$1A-PA6-PadP31)") (class "Default")
      (node (ref "U$1") (pin "P31") (pinfunction "PA6_P31") (pintype "bidirectional"))
    )
    (net (code "64") (name "unconnected-(U$1A-PA9-PadP68)") (class "Default")
      (node (ref "U$1") (pin "P68") (pinfunction "PA9_P68") (pintype "bidirectional"))
    )
    (net (code "65") (name "unconnected-(U$1A-PA10-PadP69)") (class "Default")
      (node (ref "U$1") (pin "P69") (pinfunction "PA10_P69") (pintype "bidirectional"))
    )
    (net (code "66") (name "unconnected-(U$1A-PA13-PadP72)") (class "Default")
      (node (ref "U$1") (pin "P72") (pinfunction "PA13_P72") (pintype "bidirectional"))
    )
    (net (code "67") (name "unconnected-(U$1A-PA14-PadP76)") (class "Default")
      (node (ref "U$1") (pin "P76") (pinfunction "PA14_P76") (pintype "bidirectional"))
    )
    (net (code "68") (name "unconnected-(U$1A-PA15-PadP77)") (class "Default")
      (node (ref "U$1") (pin "P77") (pinfunction "PA15_P77") (pintype "bidirectional"))
    )
    (net (code "69") (name "unconnected-(U$1B-PB0-PadP35)") (class "Default")
      (node (ref "U$1") (pin "P35") (pinfunction "PB0_P35") (pintype "bidirectional"))
    )
    (net (code "70") (name "unconnected-(U$1B-PB1-PadP36)") (class "Default")
      (node (ref "U$1") (pin "P36") (pinfunction "PB1_P36") (pintype "bidirectional"))
    )
    (net (code "71") (name "unconnected-(U$1B-PB2-PadP37)") (class "Default")
      (node (ref "U$1") (pin "P37") (pinfunction "PB2_P37") (pintype "bidirectional"))
    )
    (net (code "72") (name "unconnected-(U$1B-PB3-PadP89)") (class "Default")
      (node (ref "U$1") (pin "P89") (pinfunction "PB3_P89") (pintype "bidirectional"))
    )
    (net (code "73") (name "unconnected-(U$1B-PB4-PadP90)") (class "Default")
      (node (ref "U$1") (pin "P90") (pinfunction "PB4_P90") (pintype "bidirectional"))
    )
    (net (code "74") (name "unconnected-(U$1B-PB9-PadP96)") (class "Default")
      (node (ref "U$1") (pin "P96") (pinfunction "PB9_P96") (pintype "bidirectional"))
    )
    (net (code "75") (name "unconnected-(U$1B-PB10-PadP47)") (class "Default")
      (node (ref "U$1") (pin "P47") (pinfunction "PB10_P47") (pintype "bidirectional"))
    )
    (net (code "76") (name "unconnected-(U$1B-PB14-PadP53)") (class "Default")
      (node (ref "U$1") (pin "P53") (pinfunction "PB14_P53") (pintype "bidirectional"))
    )
    (net (code "77") (name "unconnected-(U$1B-PB15-PadP54)") (class "Default")
      (node (ref "U$1") (pin "P54") (pinfunction "PB15_P54") (pintype "bidirectional"))
    )
    (net (code "78") (name "unconnected-(U$1C-PC0-PadP15)") (class "Default")
      (node (ref "U$1") (pin "P15") (pinfunction "PC0_P15") (pintype "bidirectional"))
    )
    (net (code "79") (name "unconnected-(U$1C-PC2-PadP17)") (class "Default")
      (node (ref "U$1") (pin "P17") (pinfunction "PC2_P17") (pintype "bidirectional"))
    )
    (net (code "80") (name "unconnected-(U$1C-PC3-PadP18)") (class "Default")
      (node (ref "U$1") (pin "P18") (pinfunction "PC3_P18") (pintype "bidirectional"))
    )
    (net (code "81") (name "unconnected-(U$1C-PC6-PadP63)") (class "Default")
      (node (ref "U$1") (pin "P63") (pinfunction "PC6_P63") (pintype "bidirectional"))
    )
    (net (code "82") (name "unconnected-(U$1C-PC7-PadP64)") (class "Default")
      (node (ref "U$1") (pin "P64") (pinfunction "PC7_P64") (pintype "bidirectional"))
    )
    (net (code "83") (name "unconnected-(U$1C-PC8-PadP65)") (class "Default")
      (node (ref "U$1") (pin "P65") (pinfunction "PC8_P65") (pintype "bidirectional"))
    )
    (net (code "84") (name "unconnected-(U$1C-PC10-PadP78)") (class "Default")
      (node (ref "U$1") (pin "P78") (pinfunction "PC10_P78") (pintype "bidirectional"))
    )
    (net (code "85") (name "unconnected-(U$1C-PC11-PadP79)") (class "Default")
      (node (ref "U$1") (pin "P79") (pinfunction "PC11_P79") (pintype "bidirectional"))
    )
    (net (code "86") (name "unconnected-(U$1C-PC12-PadP80)") (class "Default")
      (node (ref "U$1") (pin "P80") (pinfunction "PC12_P80") (pintype "bidirectional"))
    )
    (net (code "87") (name "unconnected-(U$1C-PC13-PadP7)") (class "Default")
      (node (ref "U$1") (pin "P7") (pinfunction "PC13_P7") (pintype "bidirectional"))
    )
    (net (code "88") (name "unconnected-(U$1C-PC14-PadP8)") (class "Default")
      (node (ref "U$1") (pin "P8") (pinfunction "PC14_P8") (pintype "bidirectional"))
    )
    (net (code "89") (name "unconnected-(U$1C-PC15-PadP9)") (class "Default")
      (node (ref "U$1") (pin "P9") (pinfunction "PC15_P9") (pintype "bidirectional"))
    )
    (net (code "90") (name "unconnected-(U$1D-PD0-PadP81)") (class "Default")
      (node (ref "U$1") (pin "P81") (pinfunction "PD0_P81") (pintype "bidirectional"))
    )
    (net (code "91") (name "unconnected-(U$1D-PD1-PadP82)") (class "Default")
      (node (ref "U$1") (pin "P82") (pinfunction "PD1_P82") (pintype "bidirectional"))
    )
    (net (code "92") (name "unconnected-(U$1D-PD2-PadP83)") (class "Default")
      (node (ref "U$1") (pin "P83") (pinfunction "PD2_P83") (pintype "bidirectional"))
    )
    (net (code "93") (name "unconnected-(U$1D-PD3-PadP84)") (class "Default")
      (node (ref "U$1") (pin "P84") (pinfunction "PD3_P84") (pintype "bidirectional"))
    )
    (net (code "94") (name "unconnected-(U$1D-PD4-PadP85)") (class "Default")
      (node (ref "U$1") (pin "P85") (pinfunction "PD4_P85") (pintype "bidirectional"))
    )
    (net (code "95") (name "unconnected-(U$1D-PD5-PadP86)") (class "Default")
      (node (ref "U$1") (pin "P86") (pinfunction "PD5_P86") (pintype "bidirectional"))
    )
    (net (code "96") (name "unconnected-(U$1D-PD6-PadP87)") (class "Default")
      (node (ref "U$1") (pin "P87") (pinfunction "PD6_P87") (pintype "bidirectional"))
    )
    (net (code "97") (name "unconnected-(U$1D-PD7-PadP88)") (class "Default")
      (node (ref "U$1") (pin "P88") (pinfunction "PD7_P88") (pintype "bidirectional"))
    )
    (net (code "98") (name "unconnected-(U$1D-PD8-PadP55)") (class "Default")
      (node (ref "U$1") (pin "P55") (pinfunction "PD8_P55") (pintype "bidirectional"))
    )
    (net (code "99") (name "unconnected-(U$1D-PD9-PadP56)") (class "Default")
      (node (ref "U$1") (pin "P56") (pinfunction "PD9_P56") (pintype "bidirectional"))
    )
    (net (code "100") (name "unconnected-(U$1D-PD10-PadP57)") (class "Default")
      (node (ref "U$1") (pin "P57") (pinfunction "PD10_P57") (pintype "bidirectional"))
    )
    (net (code "101") (name "unconnected-(U$1D-PD15-PadP62)") (class "Default")
      (node (ref "U$1") (pin "P62") (pinfunction "PD15_P62") (pintype "bidirectional"))
    )
    (net (code "102") (name "unconnected-(U$1E-PE0-PadP97)") (class "Default")
      (node (ref "U$1") (pin "P97") (pinfunction "PE0_P97") (pintype "bidirectional"))
    )
    (net (code "103") (name "unconnected-(U$1E-PE1-PadP98)") (class "Default")
      (node (ref "U$1") (pin "P98") (pinfunction "PE1_P98") (pintype "bidirectional"))
    )
    (net (code "104") (name "unconnected-(U$1E-PE2-PadP1)") (class "Default")
      (node (ref "U$1") (pin "P1") (pinfunction "PE2_P1") (pintype "bidirectional"))
    )
    (net (code "105") (name "unconnected-(U$1E-PE3-PadP2)") (class "Default")
      (node (ref "U$1") (pin "P2") (pinfunction "PE3_P2") (pintype "bidirectional"))
    )
    (net (code "106") (name "unconnected-(U$1E-PE4-PadP3)") (class "Default")
      (node (ref "U$1") (pin "P3") (pinfunction "PE4_P3") (pintype "bidirectional"))
    )
    (net (code "107") (name "unconnected-(U$1E-PE5-PadP4)") (class "Default")
      (node (ref "U$1") (pin "P4") (pinfunction "PE5_P4") (pintype "bidirectional"))
    )
    (net (code "108") (name "unconnected-(U$1E-PE6-PadP5)") (class "Default")
      (node (ref "U$1") (pin "P5") (pinfunction "PE6_P5") (pintype "bidirectional"))
    )
    (net (code "109") (name "unconnected-(U$1E-PE7-PadP38)") (class "Default")
      (node (ref "U$1") (pin "P38") (pinfunction "PE7_P38") (pintype "bidirectional"))
    )
    (net (code "110") (name "unconnected-(U$1E-PE8-PadP39)") (class "Default")
      (node (ref "U$1") (pin "P39") (pinfunction "PE8_P39") (pintype "bidirectional"))
    )
    (net (code "111") (name "unconnected-(U$1E-PE9-PadP40)") (class "Default")
      (node (ref "U$1") (pin "P40") (pinfunction "PE9_P40") (pintype "bidirectional"))
    )
    (net (code "112") (name "unconnected-(U$1E-PE10-PadP41)") (class "Default")
      (node (ref "U$1") (pin "P41") (pinfunction "PE10_P41") (pintype "bidirectional"))
    )
    (net (code "113") (name "unconnected-(U$1E-PE11-PadP42)") (class "Default")
      (node (ref "U$1") (pin "P42") (pinfunction "PE11_P42") (pintype "bidirectional"))
    )
    (net (code "114") (name "unconnected-(U$1E-PE12-PadP43)") (class "Default")
      (node (ref "U$1") (pin "P43") (pinfunction "PE12_P43") (pintype "bidirectional"))
    )
    (net (code "115") (name "unconnected-(U$1E-PE13-PadP44)") (class "Default")
      (node (ref "U$1") (pin "P44") (pinfunction "PE13_P44") (pintype "bidirectional"))
    )
    (net (code "116") (name "unconnected-(U$1E-PE14-PadP45)") (class "Default")
      (node (ref "U$1") (pin "P45") (pinfunction "PE14_P45") (pintype "bidirectional"))
    )
    (net (code "117") (name "unconnected-(U$1E-PE15-PadP46)") (class "Default")
      (node (ref "U$1") (pin "P46") (pinfunction "PE15_P46") (pintype "bidirectional"))
    )
    (net (code "118") (name "unconnected-(U$1E-PH1-PadP13)") (class "Default")
      (node (ref "U$1") (pin "P13") (pinfunction "PH1_P13") (pintype "bidirectional"))
    )
    (net (code "119") (name "unconnected-(U$5-SHDN-Pad5)") (class "Default")
      (node (ref "U$5") (pin "5") (pinfunction "SHDN_5") (pintype "bidirectional"))
    )
    (net (code "120") (name "unconnected-(U$6-SHDN-Pad5)") (class "Default")
      (node (ref "U$6") (pin "5") (pinfunction "SHDN_5") (pintype "bidirectional"))
    )
  )
)
